# SparkFun_Bar_Graph_Breakout.net
KiCad netlist of a schematic drawn in EAGLE
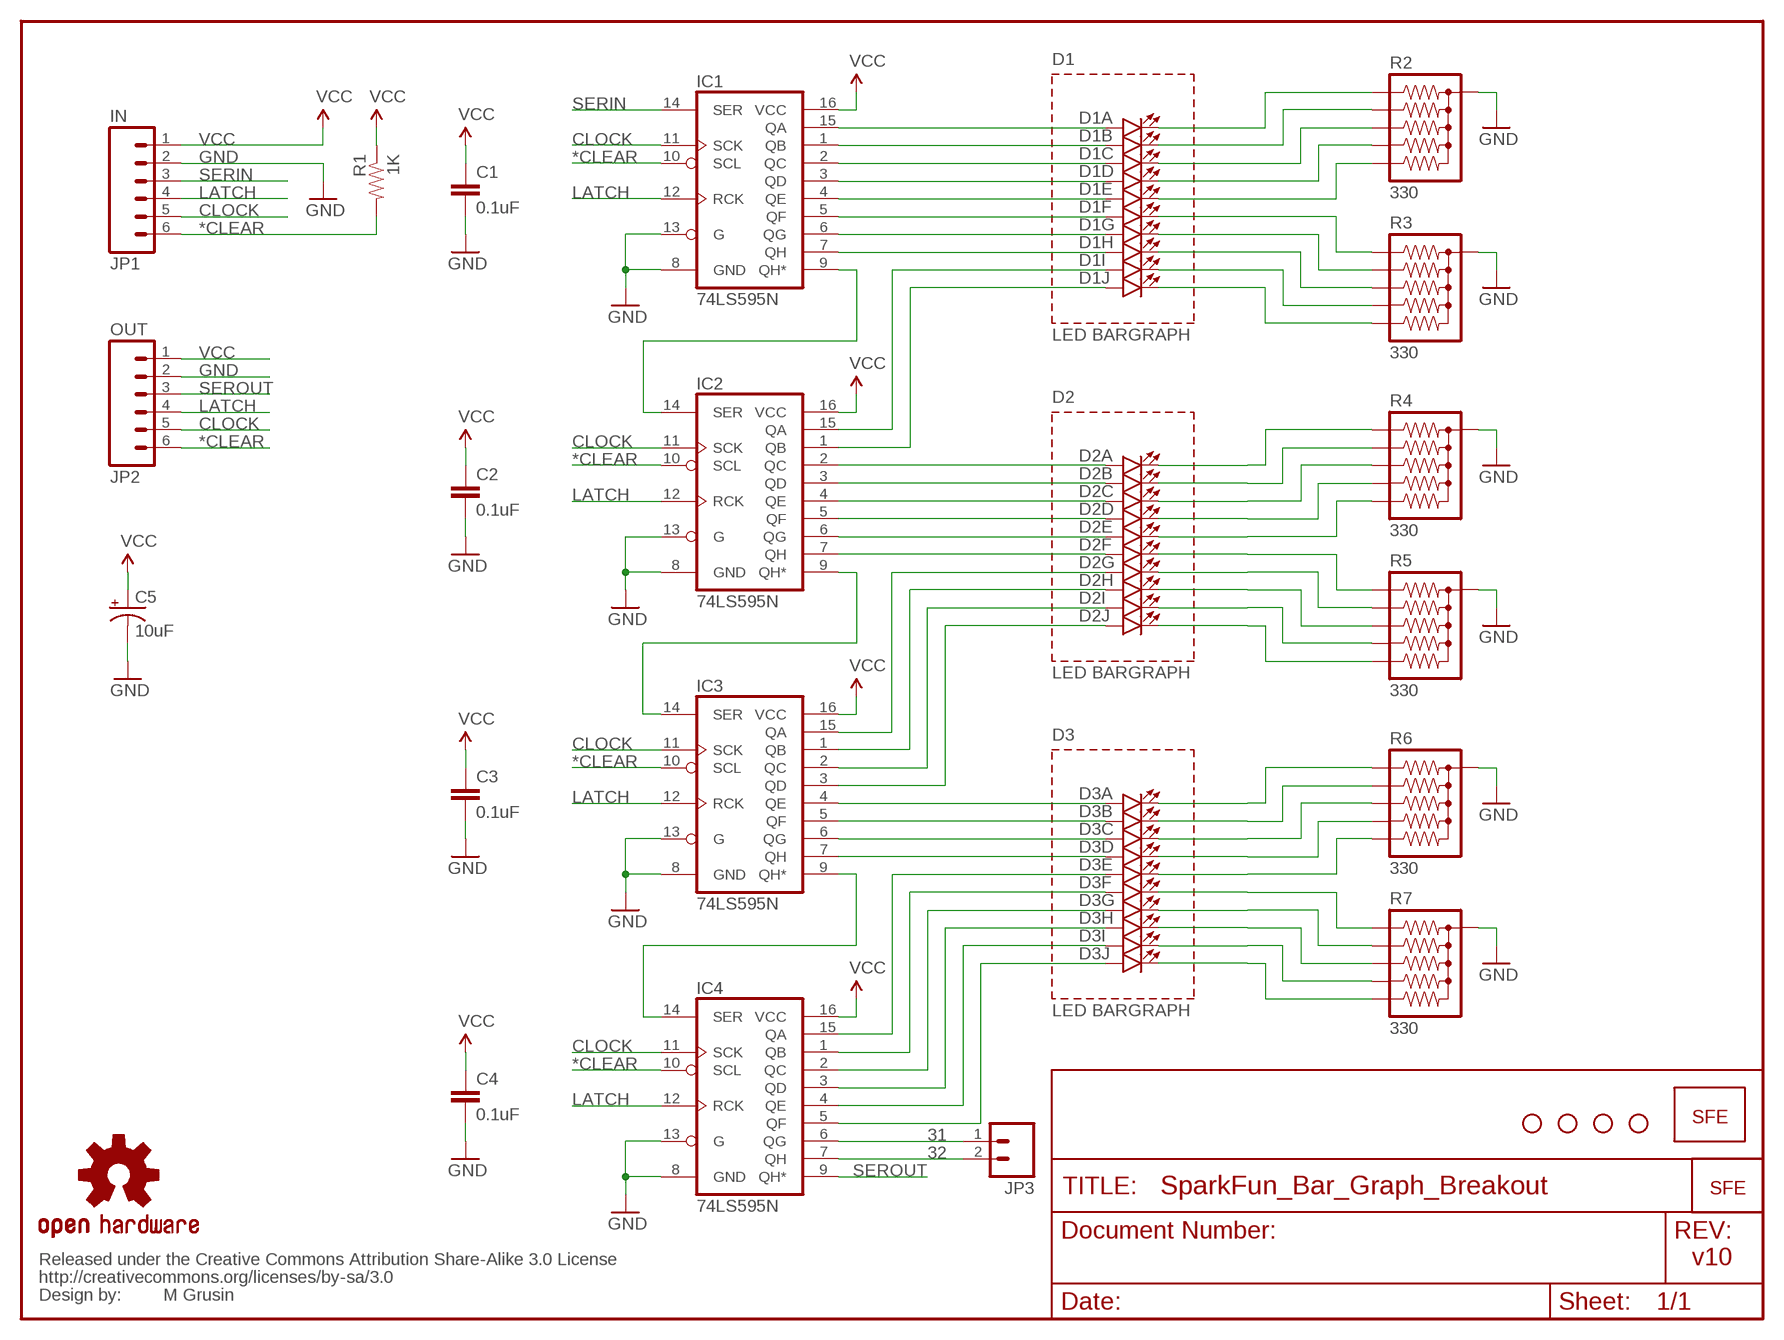
[diagram p0: schematic, sheet 1]

(export (version "E")
  (design (tool "Eeschema 10.0.6"))
  (components
    (comp (ref "C1")
      (value "0.1uF")
      (footprint "eagle-import:CAP-PTH-SMALL2")
      (libsource (lib "eagle-import") (part "CAPPTH2"))
    )
    (comp (ref "C2")
      (value "0.1uF")
      (footprint "eagle-import:CAP-PTH-SMALL2")
      (libsource (lib "eagle-import") (part "CAPPTH2"))
    )
    (comp (ref "C3")
      (value "0.1uF")
      (footprint "eagle-import:CAP-PTH-SMALL2")
      (libsource (lib "eagle-import") (part "CAPPTH2"))
    )
    (comp (ref "C4")
      (value "0.1uF")
      (footprint "eagle-import:CAP-PTH-SMALL2")
      (libsource (lib "eagle-import") (part "CAPPTH2"))
    )
    (comp (ref "C5")
      (value "10uF")
      (footprint "eagle-import:CPOL-RADIAL-10UF-25V")
      (libsource (lib "eagle-import") (part "CAP_POLPTH2"))
    )
    (comp (ref "D1")
      (value "LED_BARGRAPH_10")
      (footprint "eagle-import:LED_BARGAPH_10")
      (libsource (lib "eagle-import") (part "LED_BARGRAPH_10"))
    )
    (comp (ref "D2")
      (value "LED_BARGRAPH_10")
      (footprint "eagle-import:LED_BARGAPH_10")
      (libsource (lib "eagle-import") (part "LED_BARGRAPH_10"))
    )
    (comp (ref "D3")
      (value "LED_BARGRAPH_10")
      (footprint "eagle-import:LED_BARGAPH_10")
      (libsource (lib "eagle-import") (part "LED_BARGRAPH_10"))
    )
    (comp (ref "IC1")
      (value "74LS595N")
      (footprint "eagle-import:DIL16")
      (libsource (lib "eagle-import") (part "74595NLS"))
    )
    (comp (ref "IC2")
      (value "74LS595N")
      (footprint "eagle-import:DIL16")
      (libsource (lib "eagle-import") (part "74595NLS"))
    )
    (comp (ref "IC3")
      (value "74LS595N")
      (footprint "eagle-import:DIL16")
      (libsource (lib "eagle-import") (part "74595NLS"))
    )
    (comp (ref "IC4")
      (value "74LS595N")
      (footprint "eagle-import:DIL16")
      (libsource (lib "eagle-import") (part "74595NLS"))
    )
    (comp (ref "JP1")
      (value "IN")
      (footprint "eagle-import:1X06")
      (libsource (lib "eagle-import") (part "M06SIP"))
    )
    (comp (ref "JP2")
      (value "OUT")
      (footprint "eagle-import:1X06")
      (libsource (lib "eagle-import") (part "M06SIP"))
    )
    (comp (ref "JP3")
      (value "M02PTH")
      (footprint "eagle-import:1X02")
      (libsource (lib "eagle-import") (part "M02PTH"))
    )
    (comp (ref "LOGO1")
      (value "LOGO-SFENW2")
      (footprint "eagle-import:SFE-NEW-WEB")
      (libsource (lib "eagle-import") (part "LOGO-SFENW2"))
    )
    (comp (ref "LOGO2")
      (value "LOGO-SFESK")
      (footprint "eagle-import:SFE-LOGO-FLAME")
      (libsource (lib "eagle-import") (part "LOGO-SFESK"))
    )
    (comp (ref "R1")
      (value "1K")
      (footprint "eagle-import:AXIAL-0.3")
      (libsource (lib "eagle-import") (part "RESISTORAXIAL-0.3"))
    )
    (comp (ref "R2")
      (value "330")
      (footprint "eagle-import:RPACK-SIP-PTH-5")
      (libsource (lib "eagle-import") (part "RPACK-BUSSED-SIP-PTH-5"))
    )
    (comp (ref "R3")
      (value "330")
      (footprint "eagle-import:RPACK-SIP-PTH-5")
      (libsource (lib "eagle-import") (part "RPACK-BUSSED-SIP-PTH-5"))
    )
    (comp (ref "R4")
      (value "330")
      (footprint "eagle-import:RPACK-SIP-PTH-5")
      (libsource (lib "eagle-import") (part "RPACK-BUSSED-SIP-PTH-5"))
    )
    (comp (ref "R5")
      (value "330")
      (footprint "eagle-import:RPACK-SIP-PTH-5")
      (libsource (lib "eagle-import") (part "RPACK-BUSSED-SIP-PTH-5"))
    )
    (comp (ref "R6")
      (value "330")
      (footprint "eagle-import:RPACK-SIP-PTH-5")
      (libsource (lib "eagle-import") (part "RPACK-BUSSED-SIP-PTH-5"))
    )
    (comp (ref "R7")
      (value "330")
      (footprint "eagle-import:RPACK-SIP-PTH-5")
      (libsource (lib "eagle-import") (part "RPACK-BUSSED-SIP-PTH-5"))
    )
    (comp (ref "SO1")
      (value "STAND-OFF")
      (footprint "eagle-import:STAND-OFF")
      (libsource (lib "eagle-import") (part "STAND-OFF"))
    )
    (comp (ref "SO2")
      (value "STAND-OFF")
      (footprint "eagle-import:STAND-OFF")
      (libsource (lib "eagle-import") (part "STAND-OFF"))
    )
    (comp (ref "SO3")
      (value "STAND-OFF")
      (footprint "eagle-import:STAND-OFF")
      (libsource (lib "eagle-import") (part "STAND-OFF"))
    )
    (comp (ref "SO4")
      (value "STAND-OFF")
      (footprint "eagle-import:STAND-OFF")
      (libsource (lib "eagle-import") (part "STAND-OFF"))
    )
    (comp (ref "U$5")
      (value "OSHW-LOGOM")
      (footprint "eagle-import:OSHW-LOGO-M")
      (libsource (lib "eagle-import") (part "OSHW-LOGOM"))
    )
    (comp (ref "U$6")
      (value "CREATIVE_COMMONS")
      (footprint "eagle-import:CREATIVE_COMMONS")
      (libsource (lib "eagle-import") (part "CREATIVE_COMMONS"))
    )
  )
  (nets
    (net (code "1") (name "/*CLEAR") (class "Default")
      (node (ref "IC1") (pin "10") (pinfunction "SCL_10") (pintype "input"))
      (node (ref "IC2") (pin "10") (pinfunction "SCL_10") (pintype "input"))
      (node (ref "IC3") (pin "10") (pinfunction "SCL_10") (pintype "input"))
      (node (ref "IC4") (pin "10") (pinfunction "SCL_10") (pintype "input"))
      (node (ref "JP1") (pin "6") (pinfunction "6_6") (pintype "passive"))
      (node (ref "JP2") (pin "6") (pinfunction "6_6") (pintype "passive"))
      (node (ref "R1") (pin "P$2") (pinfunction "2_P$2") (pintype "passive"))
    )
    (net (code "2") (name "/31") (class "Default")
      (node (ref "IC4") (pin "6") (pinfunction "QG_6") (pintype "tri_state"))
      (node (ref "JP3") (pin "1") (pinfunction "1_1") (pintype "passive"))
    )
    (net (code "3") (name "/32") (class "Default")
      (node (ref "IC4") (pin "7") (pinfunction "QH_7") (pintype "tri_state"))
      (node (ref "JP3") (pin "2") (pinfunction "2_2") (pintype "passive"))
    )
    (net (code "4") (name "/CLOCK") (class "Default")
      (node (ref "IC1") (pin "11") (pinfunction "SCK_11") (pintype "input"))
      (node (ref "IC2") (pin "11") (pinfunction "SCK_11") (pintype "input"))
      (node (ref "IC3") (pin "11") (pinfunction "SCK_11") (pintype "input"))
      (node (ref "IC4") (pin "11") (pinfunction "SCK_11") (pintype "input"))
      (node (ref "JP1") (pin "5") (pinfunction "5_5") (pintype "passive"))
      (node (ref "JP2") (pin "5") (pinfunction "5_5") (pintype "passive"))
    )
    (net (code "5") (name "/LATCH") (class "Default")
      (node (ref "IC1") (pin "12") (pinfunction "RCK_12") (pintype "input"))
      (node (ref "IC2") (pin "12") (pinfunction "RCK_12") (pintype "input"))
      (node (ref "IC3") (pin "12") (pinfunction "RCK_12") (pintype "input"))
      (node (ref "IC4") (pin "12") (pinfunction "RCK_12") (pintype "input"))
      (node (ref "JP1") (pin "4") (pinfunction "4_4") (pintype "passive"))
      (node (ref "JP2") (pin "4") (pinfunction "4_4") (pintype "passive"))
    )
    (net (code "6") (name "/SERIN") (class "Default")
      (node (ref "IC1") (pin "14") (pinfunction "SER_14") (pintype "input"))
      (node (ref "JP1") (pin "3") (pinfunction "3_3") (pintype "passive"))
    )
    (net (code "7") (name "/SEROUT") (class "Default")
      (node (ref "IC4") (pin "9") (pinfunction "QH*_9") (pintype "tri_state"))
      (node (ref "JP2") (pin "3") (pinfunction "3_3") (pintype "passive"))
    )
    (net (code "8") (name "GND") (class "Default")
      (node (ref "C1") (pin "2") (pinfunction "2_2") (pintype "passive"))
      (node (ref "C2") (pin "2") (pinfunction "2_2") (pintype "passive"))
      (node (ref "C3") (pin "2") (pinfunction "2_2") (pintype "passive"))
      (node (ref "C4") (pin "2") (pinfunction "2_2") (pintype "passive"))
      (node (ref "C5") (pin "2") (pinfunction "-_2") (pintype "passive"))
      (node (ref "IC1") (pin "13") (pinfunction "G_13") (pintype "input"))
      (node (ref "IC1") (pin "8") (pinfunction "GND_8") (pintype "power_in"))
      (node (ref "IC2") (pin "13") (pinfunction "G_13") (pintype "input"))
      (node (ref "IC2") (pin "8") (pinfunction "GND_8") (pintype "power_in"))
      (node (ref "IC3") (pin "13") (pinfunction "G_13") (pintype "input"))
      (node (ref "IC3") (pin "8") (pinfunction "GND_8") (pintype "power_in"))
      (node (ref "IC4") (pin "13") (pinfunction "G_13") (pintype "input"))
      (node (ref "IC4") (pin "8") (pinfunction "GND_8") (pintype "power_in"))
      (node (ref "JP1") (pin "2") (pinfunction "2_2") (pintype "passive"))
      (node (ref "JP2") (pin "2") (pinfunction "2_2") (pintype "passive"))
      (node (ref "R2") (pin "P$1") (pinfunction "1_P$1") (pintype "passive"))
      (node (ref "R3") (pin "P$1") (pinfunction "1_P$1") (pintype "passive"))
      (node (ref "R4") (pin "P$1") (pinfunction "1_P$1") (pintype "passive"))
      (node (ref "R5") (pin "P$1") (pinfunction "1_P$1") (pintype "passive"))
      (node (ref "R6") (pin "P$1") (pinfunction "1_P$1") (pintype "passive"))
      (node (ref "R7") (pin "P$1") (pinfunction "1_P$1") (pintype "passive"))
    )
    (net (code "9") (name "Net-(D1A-A)") (class "Default")
      (node (ref "D1") (pin "1") (pinfunction "A_1") (pintype "passive"))
      (node (ref "IC1") (pin "15") (pinfunction "QA_15") (pintype "tri_state"))
    )
    (net (code "10") (name "Net-(D1A-C)") (class "Default")
      (node (ref "D1") (pin "20") (pinfunction "C_20") (pintype "passive"))
      (node (ref "R2") (pin "P$2") (pinfunction "2_P$2") (pintype "passive"))
    )
    (net (code "11") (name "Net-(D1B-A)") (class "Default")
      (node (ref "D1") (pin "2") (pinfunction "A_2") (pintype "passive"))
      (node (ref "IC1") (pin "1") (pinfunction "QB_1") (pintype "tri_state"))
    )
    (net (code "12") (name "Net-(D1B-C)") (class "Default")
      (node (ref "D1") (pin "19") (pinfunction "C_19") (pintype "passive"))
      (node (ref "R2") (pin "P$3") (pinfunction "3_P$3") (pintype "passive"))
    )
    (net (code "13") (name "Net-(D1C-A)") (class "Default")
      (node (ref "D1") (pin "3") (pinfunction "A_3") (pintype "passive"))
      (node (ref "IC1") (pin "2") (pinfunction "QC_2") (pintype "tri_state"))
    )
    (net (code "14") (name "Net-(D1C-C)") (class "Default")
      (node (ref "D1") (pin "18") (pinfunction "C_18") (pintype "passive"))
      (node (ref "R2") (pin "P$4") (pinfunction "4_P$4") (pintype "passive"))
    )
    (net (code "15") (name "Net-(D1D-A)") (class "Default")
      (node (ref "D1") (pin "4") (pinfunction "A_4") (pintype "passive"))
      (node (ref "IC1") (pin "3") (pinfunction "QD_3") (pintype "tri_state"))
    )
    (net (code "16") (name "Net-(D1D-C)") (class "Default")
      (node (ref "D1") (pin "17") (pinfunction "C_17") (pintype "passive"))
      (node (ref "R2") (pin "P$5") (pinfunction "5_P$5") (pintype "passive"))
    )
    (net (code "17") (name "Net-(D1E-A)") (class "Default")
      (node (ref "D1") (pin "5") (pinfunction "A_5") (pintype "passive"))
      (node (ref "IC1") (pin "4") (pinfunction "QE_4") (pintype "tri_state"))
    )
    (net (code "18") (name "Net-(D1E-C)") (class "Default")
      (node (ref "D1") (pin "16") (pinfunction "C_16") (pintype "passive"))
      (node (ref "R2") (pin "P$6") (pinfunction "6_P$6") (pintype "passive"))
    )
    (net (code "19") (name "Net-(D1F-A)") (class "Default")
      (node (ref "D1") (pin "6") (pinfunction "A_6") (pintype "passive"))
      (node (ref "IC1") (pin "5") (pinfunction "QF_5") (pintype "tri_state"))
    )
    (net (code "20") (name "Net-(D1F-C)") (class "Default")
      (node (ref "D1") (pin "15") (pinfunction "C_15") (pintype "passive"))
      (node (ref "R3") (pin "P$2") (pinfunction "2_P$2") (pintype "passive"))
    )
    (net (code "21") (name "Net-(D1G-A)") (class "Default")
      (node (ref "D1") (pin "7") (pinfunction "A_7") (pintype "passive"))
      (node (ref "IC1") (pin "6") (pinfunction "QG_6") (pintype "tri_state"))
    )
    (net (code "22") (name "Net-(D1G-C)") (class "Default")
      (node (ref "D1") (pin "14") (pinfunction "C_14") (pintype "passive"))
      (node (ref "R3") (pin "P$3") (pinfunction "3_P$3") (pintype "passive"))
    )
    (net (code "23") (name "Net-(D1H-A)") (class "Default")
      (node (ref "D1") (pin "8") (pinfunction "A_8") (pintype "passive"))
      (node (ref "IC1") (pin "7") (pinfunction "QH_7") (pintype "tri_state"))
    )
    (net (code "24") (name "Net-(D1H-C)") (class "Default")
      (node (ref "D1") (pin "13") (pinfunction "C_13") (pintype "passive"))
      (node (ref "R3") (pin "P$4") (pinfunction "4_P$4") (pintype "passive"))
    )
    (net (code "25") (name "Net-(D1I-A)") (class "Default")
      (node (ref "D1") (pin "9") (pinfunction "A_9") (pintype "passive"))
      (node (ref "IC2") (pin "15") (pinfunction "QA_15") (pintype "tri_state"))
    )
    (net (code "26") (name "Net-(D1I-C)") (class "Default")
      (node (ref "D1") (pin "12") (pinfunction "C_12") (pintype "passive"))
      (node (ref "R3") (pin "P$5") (pinfunction "5_P$5") (pintype "passive"))
    )
    (net (code "27") (name "Net-(D1J-A)") (class "Default")
      (node (ref "D1") (pin "10") (pinfunction "A_10") (pintype "passive"))
      (node (ref "IC2") (pin "1") (pinfunction "QB_1") (pintype "tri_state"))
    )
    (net (code "28") (name "Net-(D1J-C)") (class "Default")
      (node (ref "D1") (pin "11") (pinfunction "C_11") (pintype "passive"))
      (node (ref "R3") (pin "P$6") (pinfunction "6_P$6") (pintype "passive"))
    )
    (net (code "29") (name "Net-(D2A-A)") (class "Default")
      (node (ref "D2") (pin "1") (pinfunction "A_1") (pintype "passive"))
      (node (ref "IC2") (pin "2") (pinfunction "QC_2") (pintype "tri_state"))
    )
    (net (code "30") (name "Net-(D2A-C)") (class "Default")
      (node (ref "D2") (pin "20") (pinfunction "C_20") (pintype "passive"))
      (node (ref "R4") (pin "P$2") (pinfunction "2_P$2") (pintype "passive"))
    )
    (net (code "31") (name "Net-(D2B-A)") (class "Default")
      (node (ref "D2") (pin "2") (pinfunction "A_2") (pintype "passive"))
      (node (ref "IC2") (pin "3") (pinfunction "QD_3") (pintype "tri_state"))
    )
    (net (code "32") (name "Net-(D2B-C)") (class "Default")
      (node (ref "D2") (pin "19") (pinfunction "C_19") (pintype "passive"))
      (node (ref "R4") (pin "P$3") (pinfunction "3_P$3") (pintype "passive"))
    )
    (net (code "33") (name "Net-(D2C-A)") (class "Default")
      (node (ref "D2") (pin "3") (pinfunction "A_3") (pintype "passive"))
      (node (ref "IC2") (pin "4") (pinfunction "QE_4") (pintype "tri_state"))
    )
    (net (code "34") (name "Net-(D2C-C)") (class "Default")
      (node (ref "D2") (pin "18") (pinfunction "C_18") (pintype "passive"))
      (node (ref "R4") (pin "P$4") (pinfunction "4_P$4") (pintype "passive"))
    )
    (net (code "35") (name "Net-(D2D-A)") (class "Default")
      (node (ref "D2") (pin "4") (pinfunction "A_4") (pintype "passive"))
      (node (ref "IC2") (pin "5") (pinfunction "QF_5") (pintype "tri_state"))
    )
    (net (code "36") (name "Net-(D2D-C)") (class "Default")
      (node (ref "D2") (pin "17") (pinfunction "C_17") (pintype "passive"))
      (node (ref "R4") (pin "P$5") (pinfunction "5_P$5") (pintype "passive"))
    )
    (net (code "37") (name "Net-(D2E-A)") (class "Default")
      (node (ref "D2") (pin "5") (pinfunction "A_5") (pintype "passive"))
      (node (ref "IC2") (pin "6") (pinfunction "QG_6") (pintype "tri_state"))
    )
    (net (code "38") (name "Net-(D2E-C)") (class "Default")
      (node (ref "D2") (pin "16") (pinfunction "C_16") (pintype "passive"))
      (node (ref "R4") (pin "P$6") (pinfunction "6_P$6") (pintype "passive"))
    )
    (net (code "39") (name "Net-(D2F-A)") (class "Default")
      (node (ref "D2") (pin "6") (pinfunction "A_6") (pintype "passive"))
      (node (ref "IC2") (pin "7") (pinfunction "QH_7") (pintype "tri_state"))
    )
    (net (code "40") (name "Net-(D2F-C)") (class "Default")
      (node (ref "D2") (pin "15") (pinfunction "C_15") (pintype "passive"))
      (node (ref "R5") (pin "P$2") (pinfunction "2_P$2") (pintype "passive"))
    )
    (net (code "41") (name "Net-(D2G-A)") (class "Default")
      (node (ref "D2") (pin "7") (pinfunction "A_7") (pintype "passive"))
      (node (ref "IC3") (pin "15") (pinfunction "QA_15") (pintype "tri_state"))
    )
    (net (code "42") (name "Net-(D2G-C)") (class "Default")
      (node (ref "D2") (pin "14") (pinfunction "C_14") (pintype "passive"))
      (node (ref "R5") (pin "P$3") (pinfunction "3_P$3") (pintype "passive"))
    )
    (net (code "43") (name "Net-(D2H-A)") (class "Default")
      (node (ref "D2") (pin "8") (pinfunction "A_8") (pintype "passive"))
      (node (ref "IC3") (pin "1") (pinfunction "QB_1") (pintype "tri_state"))
    )
    (net (code "44") (name "Net-(D2H-C)") (class "Default")
      (node (ref "D2") (pin "13") (pinfunction "C_13") (pintype "passive"))
      (node (ref "R5") (pin "P$4") (pinfunction "4_P$4") (pintype "passive"))
    )
    (net (code "45") (name "Net-(D2I-A)") (class "Default")
      (node (ref "D2") (pin "9") (pinfunction "A_9") (pintype "passive"))
      (node (ref "IC3") (pin "2") (pinfunction "QC_2") (pintype "tri_state"))
    )
    (net (code "46") (name "Net-(D2I-C)") (class "Default")
      (node (ref "D2") (pin "12") (pinfunction "C_12") (pintype "passive"))
      (node (ref "R5") (pin "P$5") (pinfunction "5_P$5") (pintype "passive"))
    )
    (net (code "47") (name "Net-(D2J-A)") (class "Default")
      (node (ref "D2") (pin "10") (pinfunction "A_10") (pintype "passive"))
      (node (ref "IC3") (pin "3") (pinfunction "QD_3") (pintype "tri_state"))
    )
    (net (code "48") (name "Net-(D2J-C)") (class "Default")
      (node (ref "D2") (pin "11") (pinfunction "C_11") (pintype "passive"))
      (node (ref "R5") (pin "P$6") (pinfunction "6_P$6") (pintype "passive"))
    )
    (net (code "49") (name "Net-(D3A-A)") (class "Default")
      (node (ref "D3") (pin "1") (pinfunction "A_1") (pintype "passive"))
      (node (ref "IC3") (pin "4") (pinfunction "QE_4") (pintype "tri_state"))
    )
    (net (code "50") (name "Net-(D3A-C)") (class "Default")
      (node (ref "D3") (pin "20") (pinfunction "C_20") (pintype "passive"))
      (node (ref "R6") (pin "P$2") (pinfunction "2_P$2") (pintype "passive"))
    )
    (net (code "51") (name "Net-(D3B-A)") (class "Default")
      (node (ref "D3") (pin "2") (pinfunction "A_2") (pintype "passive"))
      (node (ref "IC3") (pin "5") (pinfunction "QF_5") (pintype "tri_state"))
    )
    (net (code "52") (name "Net-(D3B-C)") (class "Default")
      (node (ref "D3") (pin "19") (pinfunction "C_19") (pintype "passive"))
      (node (ref "R6") (pin "P$3") (pinfunction "3_P$3") (pintype "passive"))
    )
    (net (code "53") (name "Net-(D3C-A)") (class "Default")
      (node (ref "D3") (pin "3") (pinfunction "A_3") (pintype "passive"))
      (node (ref "IC3") (pin "6") (pinfunction "QG_6") (pintype "tri_state"))
    )
    (net (code "54") (name "Net-(D3C-C)") (class "Default")
      (node (ref "D3") (pin "18") (pinfunction "C_18") (pintype "passive"))
      (node (ref "R6") (pin "P$4") (pinfunction "4_P$4") (pintype "passive"))
    )
    (net (code "55") (name "Net-(D3D-A)") (class "Default")
      (node (ref "D3") (pin "4") (pinfunction "A_4") (pintype "passive"))
      (node (ref "IC3") (pin "7") (pinfunction "QH_7") (pintype "tri_state"))
    )
    (net (code "56") (name "Net-(D3D-C)") (class "Default")
      (node (ref "D3") (pin "17") (pinfunction "C_17") (pintype "passive"))
      (node (ref "R6") (pin "P$5") (pinfunction "5_P$5") (pintype "passive"))
    )
    (net (code "57") (name "Net-(D3E-A)") (class "Default")
      (node (ref "D3") (pin "5") (pinfunction "A_5") (pintype "passive"))
      (node (ref "IC4") (pin "15") (pinfunction "QA_15") (pintype "tri_state"))
    )
    (net (code "58") (name "Net-(D3E-C)") (class "Default")
      (node (ref "D3") (pin "16") (pinfunction "C_16") (pintype "passive"))
      (node (ref "R6") (pin "P$6") (pinfunction "6_P$6") (pintype "passive"))
    )
    (net (code "59") (name "Net-(D3F-A)") (class "Default")
      (node (ref "D3") (pin "6") (pinfunction "A_6") (pintype "passive"))
      (node (ref "IC4") (pin "1") (pinfunction "QB_1") (pintype "tri_state"))
    )
    (net (code "60") (name "Net-(D3F-C)") (class "Default")
      (node (ref "D3") (pin "15") (pinfunction "C_15") (pintype "passive"))
      (node (ref "R7") (pin "P$2") (pinfunction "2_P$2") (pintype "passive"))
    )
    (net (code "61") (name "Net-(D3G-A)") (class "Default")
      (node (ref "D3") (pin "7") (pinfunction "A_7") (pintype "passive"))
      (node (ref "IC4") (pin "2") (pinfunction "QC_2") (pintype "tri_state"))
    )
    (net (code "62") (name "Net-(D3G-C)") (class "Default")
      (node (ref "D3") (pin "14") (pinfunction "C_14") (pintype "passive"))
      (node (ref "R7") (pin "P$3") (pinfunction "3_P$3") (pintype "passive"))
    )
    (net (code "63") (name "Net-(D3H-A)") (class "Default")
      (node (ref "D3") (pin "8") (pinfunction "A_8") (pintype "passive"))
      (node (ref "IC4") (pin "3") (pinfunction "QD_3") (pintype "tri_state"))
    )
    (net (code "64") (name "Net-(D3H-C)") (class "Default")
      (node (ref "D3") (pin "13") (pinfunction "C_13") (pintype "passive"))
      (node (ref "R7") (pin "P$4") (pinfunction "4_P$4") (pintype "passive"))
    )
    (net (code "65") (name "Net-(D3I-A)") (class "Default")
      (node (ref "D3") (pin "9") (pinfunction "A_9") (pintype "passive"))
      (node (ref "IC4") (pin "4") (pinfunction "QE_4") (pintype "tri_state"))
    )
    (net (code "66") (name "Net-(D3I-C)") (class "Default")
      (node (ref "D3") (pin "12") (pinfunction "C_12") (pintype "passive"))
      (node (ref "R7") (pin "P$5") (pinfunction "5_P$5") (pintype "passive"))
    )
    (net (code "67") (name "Net-(D3J-A)") (class "Default")
      (node (ref "D3") (pin "10") (pinfunction "A_10") (pintype "passive"))
      (node (ref "IC4") (pin "5") (pinfunction "QF_5") (pintype "tri_state"))
    )
    (net (code "68") (name "Net-(D3J-C)") (class "Default")
      (node (ref "D3") (pin "11") (pinfunction "C_11") (pintype "passive"))
      (node (ref "R7") (pin "P$6") (pinfunction "6_P$6") (pintype "passive"))
    )
    (net (code "69") (name "Net-(IC1-QH*)") (class "Default")
      (node (ref "IC1") (pin "9") (pinfunction "QH*_9") (pintype "tri_state"))
      (node (ref "IC2") (pin "14") (pinfunction "SER_14") (pintype "input"))
    )
    (net (code "70") (name "Net-(IC2-QH*)") (class "Default")
      (node (ref "IC2") (pin "9") (pinfunction "QH*_9") (pintype "tri_state"))
      (node (ref "IC3") (pin "14") (pinfunction "SER_14") (pintype "input"))
    )
    (net (code "71") (name "Net-(IC3-QH*)") (class "Default")
      (node (ref "IC3") (pin "9") (pinfunction "QH*_9") (pintype "tri_state"))
      (node (ref "IC4") (pin "14") (pinfunction "SER_14") (pintype "input"))
    )
    (net (code "72") (name "VCC") (class "Default")
      (node (ref "C1") (pin "1") (pinfunction "1_1") (pintype "passive"))
      (node (ref "C2") (pin "1") (pinfunction "1_1") (pintype "passive"))
      (node (ref "C3") (pin "1") (pinfunction "1_1") (pintype "passive"))
      (node (ref "C4") (pin "1") (pinfunction "1_1") (pintype "passive"))
      (node (ref "C5") (pin "1") (pinfunction "+_1") (pintype "passive"))
      (node (ref "IC1") (pin "16") (pinfunction "VCC_16") (pintype "power_in"))
      (node (ref "IC2") (pin "16") (pinfunction "VCC_16") (pintype "power_in"))
      (node (ref "IC3") (pin "16") (pinfunction "VCC_16") (pintype "power_in"))
      (node (ref "IC4") (pin "16") (pinfunction "VCC_16") (pintype "power_in"))
      (node (ref "JP1") (pin "1") (pinfunction "1_1") (pintype "passive"))
      (node (ref "JP2") (pin "1") (pinfunction "1_1") (pintype "passive"))
      (node (ref "R1") (pin "P$1") (pinfunction "1_P$1") (pintype "passive"))
    )
  )
)
